# SCH_ESP32-v1_2025-11-18.net
KiCad netlist of a schematic drawn in EasyEDA
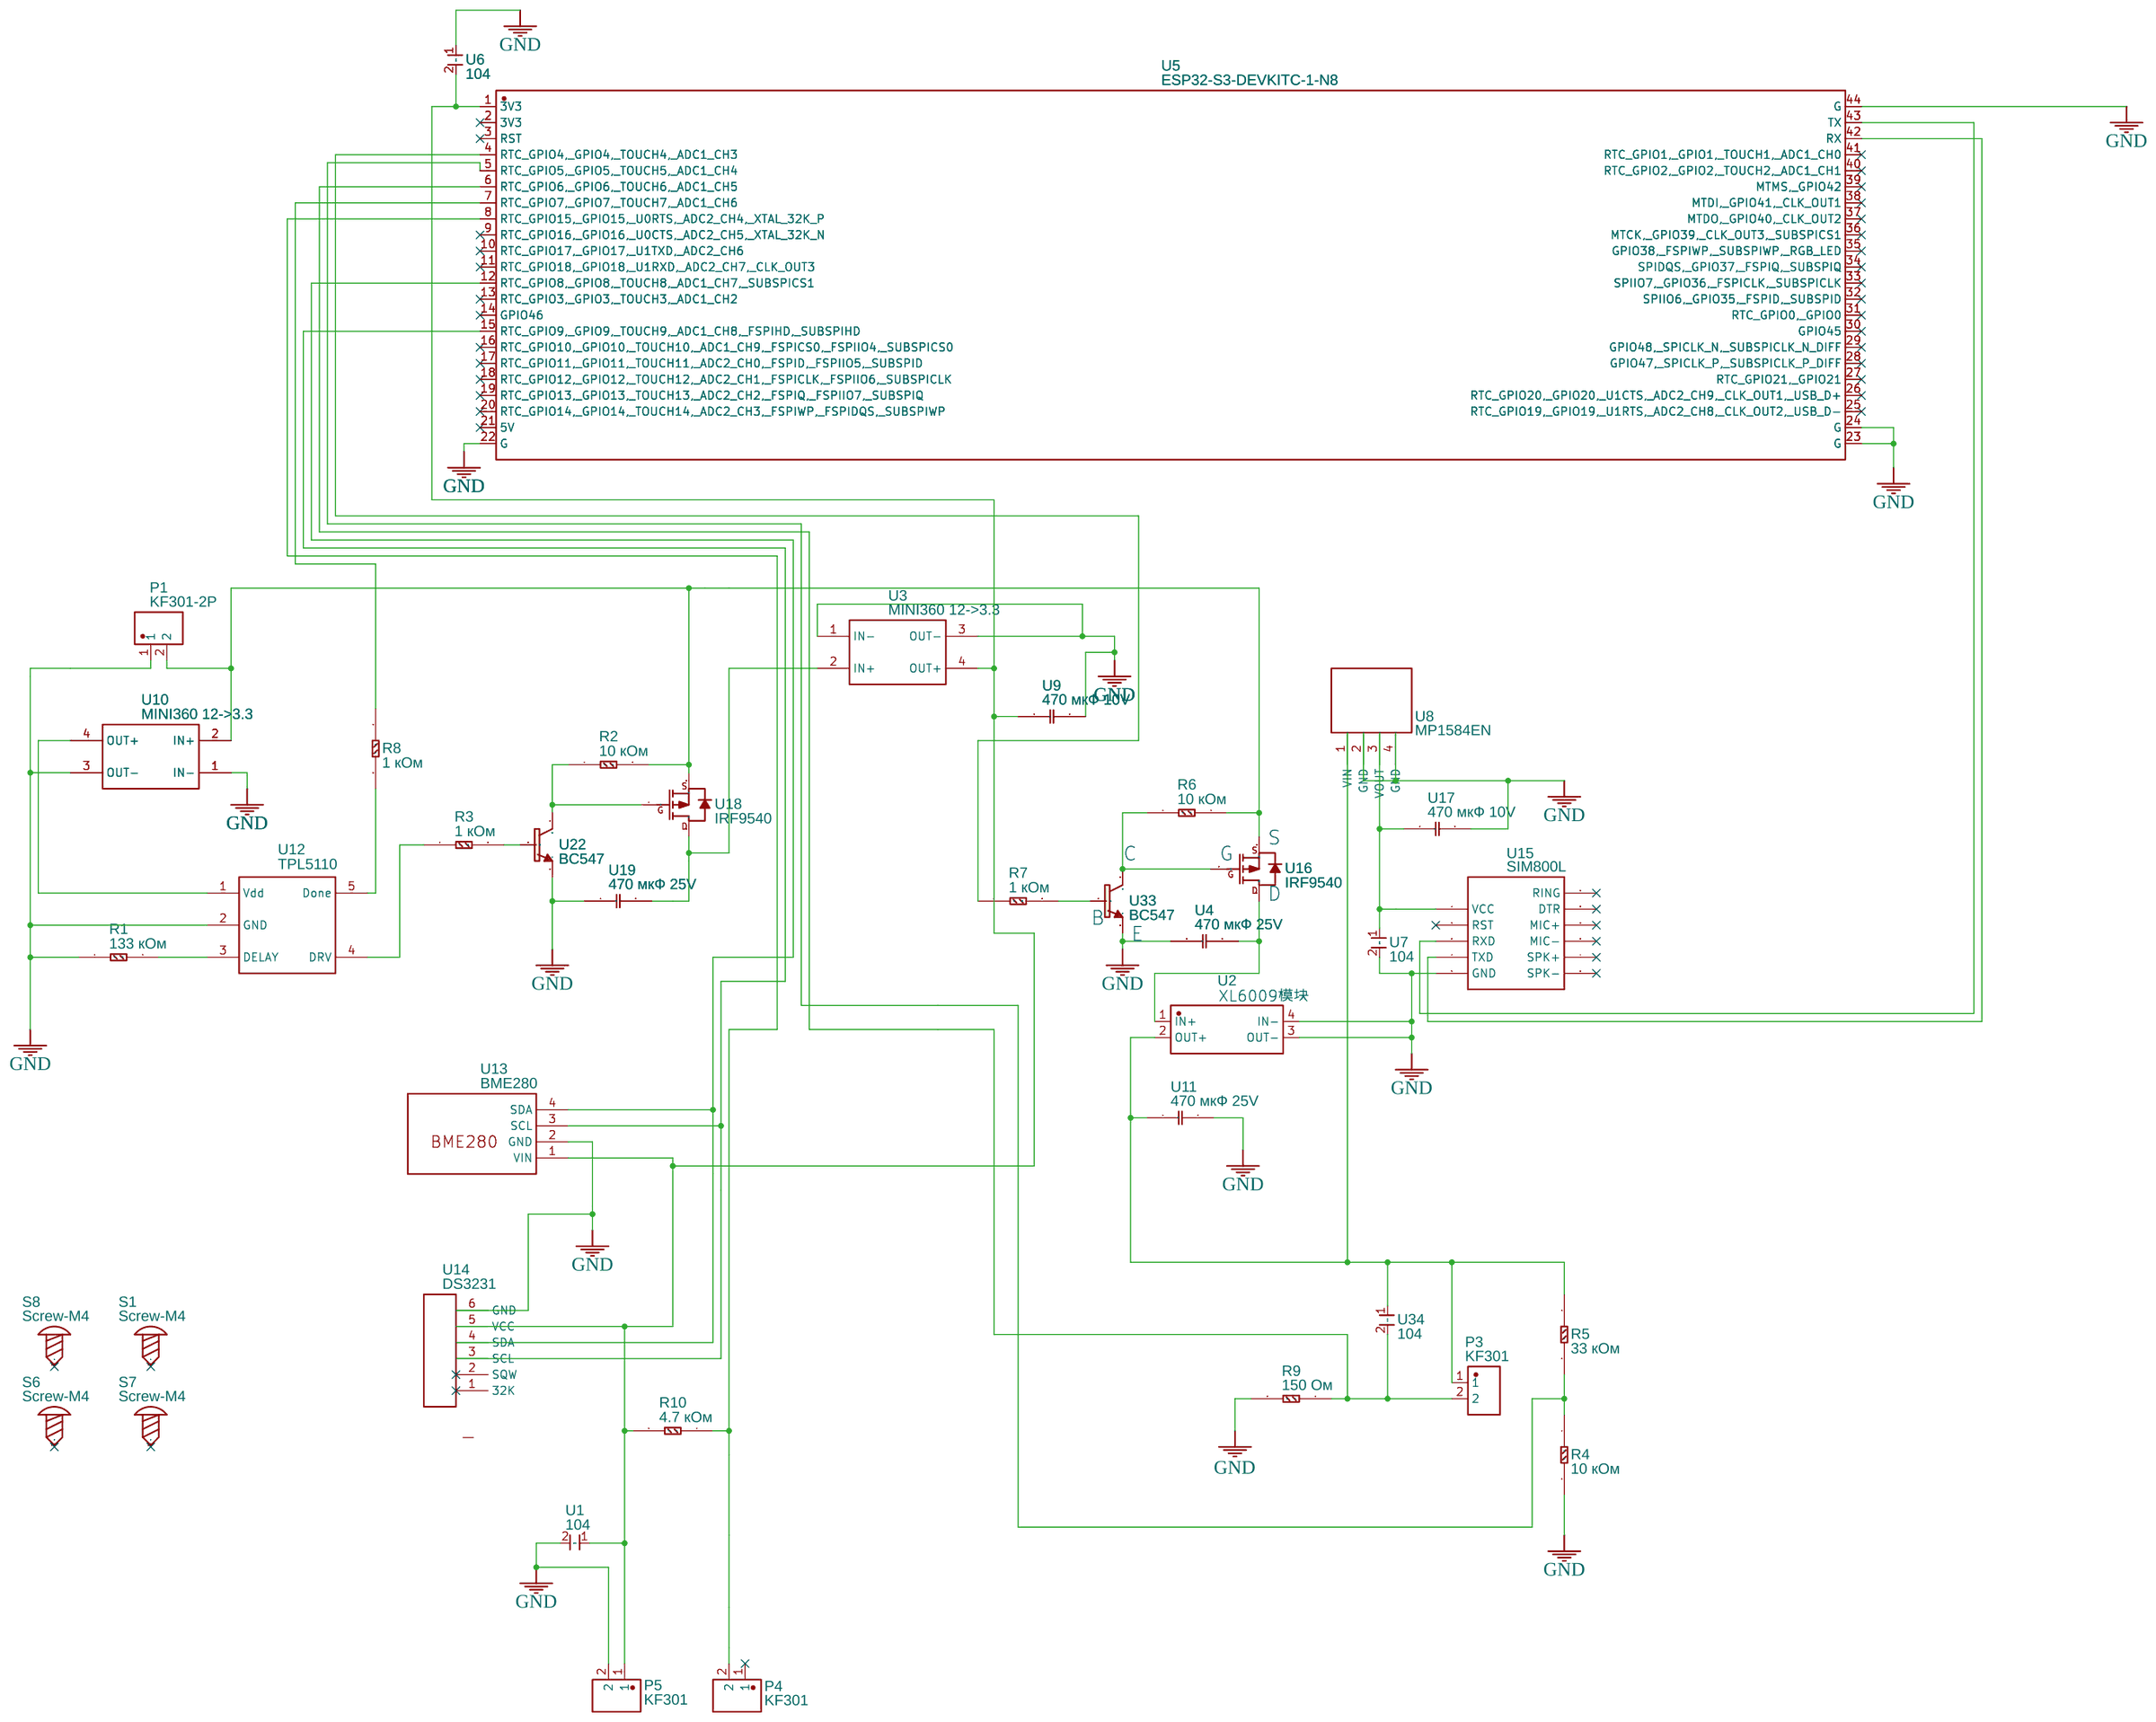
[diagram p0: schematic sheet]

(export (version "E")
  (design (tool "Eeschema 10.0.6"))
  (components
    (comp (ref "P1")
      (value "KF301-2P")
      (fields (field (name "Manufacturer Part") "KF301-2P接线端子"))
      (libsource (lib "") (part "KF301-2P VCC Y GND_2"))
    )
    (comp (ref "P3")
      (value "KF301")
      (fields (field (name "Manufacturer Part") "KF301-2P接线端子"))
      (libsource (lib "") (part "KF301-2P VCC Y GND"))
    )
    (comp (ref "P4")
      (value "KF301")
      (fields (field (name "Manufacturer Part") "KF301-2P接线端子"))
      (libsource (lib "") (part "KF301-2P VCC Y GND_1"))
    )
    (comp (ref "P5")
      (value "KF301")
      (fields (field (name "Manufacturer Part") "KF301-2P接线端子"))
      (libsource (lib "") (part "KF301-2P VCC Y GND_1"))
    )
    (comp (ref "R1") (value "133 кОм") (libsource (lib "") (part "R__1")))
    (comp (ref "R2") (value "10 кОм") (libsource (lib "") (part "R__1")))
    (comp (ref "R3") (value "1 кОм") (libsource (lib "") (part "R__1")))
    (comp (ref "R4") (value "10 кОм") (libsource (lib "") (part "R__2")))
    (comp (ref "R5") (value "33 кОм") (libsource (lib "") (part "R__2")))
    (comp (ref "R6") (value "10 кОм") (libsource (lib "") (part "R__1")))
    (comp (ref "R7") (value "1 кОм") (libsource (lib "") (part "R__1")))
    (comp (ref "R8") (value "1 кОм") (libsource (lib "") (part "R__2")))
    (comp (ref "R9") (value "150 Ом") (libsource (lib "") (part "R_")))
    (comp (ref "R10") (value "4.7 кОм") (libsource (lib "") (part "R_")))
    (comp (ref "S1") (value "Screw-M4") (libsource (lib "") (part "Screw-M4")))
    (comp (ref "S6") (value "Screw-M4") (libsource (lib "") (part "Screw-M4")))
    (comp (ref "S7") (value "Screw-M4") (libsource (lib "") (part "Screw-M4")))
    (comp (ref "S8") (value "Screw-M4") (libsource (lib "") (part "Screw-M4")))
    (comp (ref "U1")
      (value "104")
      (fields (field (name "Manufacturer") "Fe"))
      (libsource (lib "") (part "104_1"))
    )
    (comp (ref "U2")
      (value "XL6009模块")
      (fields (field (name "Manufacturer Part") "xl6009模块"))
      (libsource (lib "") (part "XL6009模块"))
    )
    (comp (ref "U3")
      (value "MINI360 12->3.3")
      (fields (field (name "Manufacturer Part") "Mini360"))
      (libsource (lib "") (part "MINI360BUCK_1"))
    )
    (comp (ref "U4") (value "470 мкФ 25V") (libsource (lib "") (part "C_")))
    (comp (ref "U5")
      (value "ESP32-S3-DEVKITC-1-N8")
      (fields (field (name "Manufacturer") "ESPRESSIF(乐鑫)"))
      (libsource (lib "") (part "ESP32-S3-DEVKITC-1-N8"))
    )
    (comp (ref "U6")
      (value "104")
      (fields (field (name "Manufacturer") "Fe"))
      (libsource (lib "") (part "104"))
    )
    (comp (ref "U7")
      (value "104")
      (fields (field (name "Manufacturer") "Fe"))
      (libsource (lib "") (part "104"))
    )
    (comp (ref "U8") (value "MP1584EN") (libsource (lib "") (part "MP1584EN")))
    (comp (ref "U9") (value "470 мкФ 10V") (libsource (lib "") (part "C_")))
    (comp (ref "U10")
      (value "MINI360 12->3.3")
      (fields (field (name "Manufacturer Part") "Mini360"))
      (libsource (lib "") (part "MINI360BUCK"))
    )
    (comp (ref "U11") (value "470 мкФ 25V") (libsource (lib "") (part "C_")))
    (comp (ref "U12")
      (value "TPL5110")
      (fields (field (name "Manufacturer Part") "3435"))
      (libsource (lib "") (part "ADAFRUIT TPL5110 BREAKOUT"))
    )
    (comp (ref "U13") (value "BME280") (libsource (lib "") (part "BME280")))
    (comp (ref "U14") (value "DS3231") (libsource (lib "") (part "DS3231 upright")))
    (comp (ref "U15") (value "SIM800L") (libsource (lib "") (part "SIM800L")))
    (comp (ref "U16") (value "IRF9540") (libsource (lib "") (part "IRF9540")))
    (comp (ref "U17") (value "470 мкФ 10V") (libsource (lib "") (part "C_")))
    (comp (ref "U18") (value "IRF9540") (libsource (lib "") (part "IRF9540")))
    (comp (ref "U19") (value "470 мкФ 25V") (libsource (lib "") (part "C_")))
    (comp (ref "U22") (value "BC547") (libsource (lib "") (part "BC547")))
    (comp (ref "U33") (value "BC547") (libsource (lib "") (part "BC547")))
    (comp (ref "U34")
      (value "104")
      (fields (field (name "Manufacturer") "Fe"))
      (libsource (lib "") (part "104"))
    )
  )
  (nets
    (net (code "1") (name "GND") (class "Default")
      (node (ref "P1") (pin "1") (pinfunction "1_1") (pintype "unspecified"))
      (node (ref "P5") (pin "2") (pinfunction "2_2") (pintype "unspecified"))
      (node (ref "R1") (pin "1") (pinfunction "1_1") (pintype "unspecified"))
      (node (ref "R4") (pin "2") (pinfunction "2_2") (pintype "unspecified"))
      (node (ref "R9") (pin "2") (pinfunction "2_2") (pintype "unspecified"))
      (node (ref "U1") (pin "2") (pinfunction "2_2") (pintype "unspecified"))
      (node (ref "U10") (pin "1") (pinfunction "IN-_1") (pintype "unspecified"))
      (node (ref "U10") (pin "3") (pinfunction "OUT-_3") (pintype "unspecified"))
      (node (ref "U11") (pin "2") (pinfunction "2_2") (pintype "unspecified"))
      (node (ref "U12") (pin "2") (pinfunction "GND_2") (pintype "unspecified"))
      (node (ref "U13") (pin "2") (pinfunction "GND_2") (pintype "unspecified"))
      (node (ref "U14") (pin "6") (pinfunction "GND_6") (pintype "unspecified"))
      (node (ref "U15") (pin "5") (pinfunction "GND_5") (pintype "unspecified"))
      (node (ref "U17") (pin "2") (pinfunction "2_2") (pintype "unspecified"))
      (node (ref "U19") (pin "1") (pinfunction "1_1") (pintype "unspecified"))
      (node (ref "U2") (pin "3") (pinfunction "OUT-_3") (pintype "unspecified"))
      (node (ref "U2") (pin "4") (pinfunction "IN-_4") (pintype "unspecified"))
      (node (ref "U22") (pin "3") (pinfunction "E_3") (pintype "unspecified"))
      (node (ref "U3") (pin "1") (pinfunction "IN-_1") (pintype "unspecified"))
      (node (ref "U3") (pin "3") (pinfunction "OUT-_3") (pintype "unspecified"))
      (node (ref "U33") (pin "3") (pinfunction "E_3") (pintype "unspecified"))
      (node (ref "U4") (pin "1") (pinfunction "1_1") (pintype "unspecified"))
      (node (ref "U5") (pin "22") (pinfunction "G_22") (pintype "unspecified"))
      (node (ref "U5") (pin "23") (pinfunction "G_23") (pintype "unspecified"))
      (node (ref "U5") (pin "24") (pinfunction "G_24") (pintype "unspecified"))
      (node (ref "U5") (pin "44") (pinfunction "G_44") (pintype "unspecified"))
      (node (ref "U6") (pin "1") (pinfunction "1_1") (pintype "unspecified"))
      (node (ref "U7") (pin "2") (pinfunction "2_2") (pintype "unspecified"))
      (node (ref "U8") (pin "2") (pinfunction "GND_2") (pintype "unspecified"))
      (node (ref "U8") (pin "4") (pinfunction "GND_4") (pintype "unspecified"))
      (node (ref "U9") (pin "2") (pinfunction "2_2") (pintype "unspecified"))
    )
    (net (code "2") (name "Net-(U2-OUT+)") (class "Default")
      (node (ref "P3") (pin "1") (pinfunction "1_1") (pintype "unspecified"))
      (node (ref "R5") (pin "1") (pinfunction "1_1") (pintype "unspecified"))
      (node (ref "U11") (pin "1") (pinfunction "1_1") (pintype "unspecified"))
      (node (ref "U2") (pin "2") (pinfunction "OUT+_2") (pintype "unspecified"))
      (node (ref "U34") (pin "1") (pinfunction "1_1") (pintype "unspecified"))
      (node (ref "U8") (pin "1") (pinfunction "VIN_1") (pintype "unspecified"))
    )
    (net (code "3") (name "Net-(U5-RTC_GPIO4,_GPIO4,_TOUCH4,_ADC1_CH3)") (class "Default")
      (node (ref "R7") (pin "1") (pinfunction "1_1") (pintype "unspecified"))
      (node (ref "U5") (pin "4") (pinfunction "RTC_GPIO4,_GPIO4,_TOUCH4,_ADC1_CH3_4") (pintype "unspecified"))
    )
    (net (code "4") (name "Net-(U5-RTC_GPIO5,_GPIO5,_TOUCH5,_ADC1_CH4)") (class "Default")
      (node (ref "R4") (pin "1") (pinfunction "1_1") (pintype "unspecified"))
      (node (ref "R5") (pin "2") (pinfunction "2_2") (pintype "unspecified"))
      (node (ref "U5") (pin "5") (pinfunction "RTC_GPIO5,_GPIO5,_TOUCH5,_ADC1_CH4_5") (pintype "unspecified"))
    )
    (net (code "5") (name "Net-(U5-RTC_GPIO6,_GPIO6,_TOUCH6,_ADC1_CH5)") (class "Default")
      (node (ref "P3") (pin "2") (pinfunction "2_2") (pintype "unspecified"))
      (node (ref "R9") (pin "1") (pinfunction "1_1") (pintype "unspecified"))
      (node (ref "U34") (pin "2") (pinfunction "2_2") (pintype "unspecified"))
      (node (ref "U5") (pin "6") (pinfunction "RTC_GPIO6,_GPIO6,_TOUCH6,_ADC1_CH5_6") (pintype "unspecified"))
    )
    (net (code "6") (name "Net-(U5-RTC_GPIO7,_GPIO7,_TOUCH7,_ADC1_CH6)") (class "Default")
      (node (ref "R8") (pin "1") (pinfunction "1_1") (pintype "unspecified"))
      (node (ref "U5") (pin "7") (pinfunction "RTC_GPIO7,_GPIO7,_TOUCH7,_ADC1_CH6_7") (pintype "unspecified"))
    )
    (net (code "7") (name "Net-(U5-RTC_GPIO15,_GPIO15,_U0RTS,_ADC2_CH4,_XTAL_32K_P)") (class "Default")
      (node (ref "P4") (pin "2") (pinfunction "2_2") (pintype "unspecified"))
      (node (ref "R10") (pin "1") (pinfunction "1_1") (pintype "unspecified"))
      (node (ref "U5") (pin "8") (pinfunction "RTC_GPIO15,_GPIO15,_U0RTS,_ADC2_CH4,_XTAL_32K_P_8") (pintype "unspecified"))
    )
    (net (code "8") (name "Net-(U10-IN+)") (class "Default")
      (node (ref "P1") (pin "2") (pinfunction "2_2") (pintype "unspecified"))
      (node (ref "R2") (pin "2") (pinfunction "2_2") (pintype "unspecified"))
      (node (ref "R6") (pin "2") (pinfunction "2_2") (pintype "unspecified"))
      (node (ref "U10") (pin "2") (pinfunction "IN+_2") (pintype "unspecified"))
      (node (ref "U16") (pin "3") (pinfunction "S_3") (pintype "unspecified"))
      (node (ref "U18") (pin "3") (pinfunction "S_3") (pintype "unspecified"))
    )
    (net (code "9") (name "Net-(U10-OUT+)") (class "Default")
      (node (ref "U10") (pin "4") (pinfunction "OUT+_4") (pintype "unspecified"))
      (node (ref "U12") (pin "1") (pinfunction "Vdd_1") (pintype "unspecified"))
    )
    (net (code "10") (name "Net-(U12-DELAY)") (class "Default")
      (node (ref "R1") (pin "2") (pinfunction "2_2") (pintype "unspecified"))
      (node (ref "U12") (pin "3") (pinfunction "DELAY_3") (pintype "unspecified"))
    )
    (net (code "11") (name "Net-(U12-DRV)") (class "Default")
      (node (ref "R3") (pin "1") (pinfunction "1_1") (pintype "unspecified"))
      (node (ref "U12") (pin "4") (pinfunction "DRV_4") (pintype "unspecified"))
    )
    (net (code "12") (name "Net-(U12-Done)") (class "Default")
      (node (ref "R8") (pin "2") (pinfunction "2_2") (pintype "unspecified"))
      (node (ref "U12") (pin "5") (pinfunction "Done_5") (pintype "unspecified"))
    )
    (net (code "13") (name "Net-(U13-SCL)") (class "Default")
      (node (ref "U13") (pin "3") (pinfunction "SCL_3") (pintype "unspecified"))
      (node (ref "U14") (pin "3") (pinfunction "SCL_3") (pintype "unspecified"))
      (node (ref "U5") (pin "15") (pinfunction "RTC_GPIO9,_GPIO9,_TOUCH9,_ADC1_CH8,_FSPIHD,_SUBSPIHD_15") (pintype "unspecified"))
    )
    (net (code "14") (name "Net-(U13-SDA)") (class "Default")
      (node (ref "U13") (pin "4") (pinfunction "SDA_4") (pintype "unspecified"))
      (node (ref "U14") (pin "4") (pinfunction "SDA_4") (pintype "unspecified"))
      (node (ref "U5") (pin "12") (pinfunction "RTC_GPIO8,_GPIO8,_TOUCH8,_ADC1_CH7,_SUBSPICS1_12") (pintype "unspecified"))
    )
    (net (code "15") (name "Net-(U13-VIN)") (class "Default")
      (node (ref "P5") (pin "1") (pinfunction "1_1") (pintype "unspecified"))
      (node (ref "R10") (pin "2") (pinfunction "2_2") (pintype "unspecified"))
      (node (ref "U1") (pin "1") (pinfunction "1_1") (pintype "unspecified"))
      (node (ref "U13") (pin "1") (pinfunction "VIN_1") (pintype "unspecified"))
      (node (ref "U14") (pin "5") (pinfunction "VCC_5") (pintype "unspecified"))
      (node (ref "U3") (pin "4") (pinfunction "OUT+_4") (pintype "unspecified"))
      (node (ref "U5") (pin "1") (pinfunction "3V3_1") (pintype "unspecified"))
      (node (ref "U6") (pin "2") (pinfunction "2_2") (pintype "unspecified"))
      (node (ref "U9") (pin "1") (pinfunction "1_1") (pintype "unspecified"))
    )
    (net (code "16") (name "Net-(U15-RXD)") (class "Default")
      (node (ref "U15") (pin "3") (pinfunction "RXD_3") (pintype "unspecified"))
      (node (ref "U5") (pin "43") (pinfunction "TX_43") (pintype "unspecified"))
    )
    (net (code "17") (name "Net-(U15-TXD)") (class "Default")
      (node (ref "U15") (pin "4") (pinfunction "TXD_4") (pintype "unspecified"))
      (node (ref "U5") (pin "42") (pinfunction "RX_42") (pintype "unspecified"))
    )
    (net (code "18") (name "Net-(U15-VCC)") (class "Default")
      (node (ref "U15") (pin "1") (pinfunction "VCC_1") (pintype "unspecified"))
      (node (ref "U17") (pin "1") (pinfunction "1_1") (pintype "unspecified"))
      (node (ref "U7") (pin "1") (pinfunction "1_1") (pintype "unspecified"))
      (node (ref "U8") (pin "3") (pinfunction "VOUT_3") (pintype "unspecified"))
    )
    (net (code "19") (name "Net-(U16-D)") (class "Default")
      (node (ref "U16") (pin "2") (pinfunction "D_2") (pintype "unspecified"))
      (node (ref "U2") (pin "1") (pinfunction "IN+_1") (pintype "unspecified"))
      (node (ref "U4") (pin "2") (pinfunction "2_2") (pintype "unspecified"))
    )
    (net (code "20") (name "Net-(U16-G)") (class "Default")
      (node (ref "R6") (pin "1") (pinfunction "1_1") (pintype "unspecified"))
      (node (ref "U16") (pin "1") (pinfunction "G_1") (pintype "unspecified"))
      (node (ref "U33") (pin "1") (pinfunction "C_1") (pintype "unspecified"))
    )
    (net (code "21") (name "Net-(U18-D)") (class "Default")
      (node (ref "U18") (pin "2") (pinfunction "D_2") (pintype "unspecified"))
      (node (ref "U19") (pin "2") (pinfunction "2_2") (pintype "unspecified"))
      (node (ref "U3") (pin "2") (pinfunction "IN+_2") (pintype "unspecified"))
    )
    (net (code "22") (name "Net-(U18-G)") (class "Default")
      (node (ref "R2") (pin "1") (pinfunction "1_1") (pintype "unspecified"))
      (node (ref "U18") (pin "1") (pinfunction "G_1") (pintype "unspecified"))
      (node (ref "U22") (pin "1") (pinfunction "C_1") (pintype "unspecified"))
    )
    (net (code "23") (name "Net-(U22-B)") (class "Default")
      (node (ref "R3") (pin "2") (pinfunction "2_2") (pintype "unspecified"))
      (node (ref "U22") (pin "2") (pinfunction "B_2") (pintype "unspecified"))
    )
    (net (code "24") (name "Net-(U33-B)") (class "Default")
      (node (ref "R7") (pin "2") (pinfunction "2_2") (pintype "unspecified"))
      (node (ref "U33") (pin "2") (pinfunction "B_2") (pintype "unspecified"))
    )
    (net (code "25") (name "unconnected-(P4-Pad1)") (class "Default")
      (node (ref "P4") (pin "1") (pinfunction "1_1") (pintype "unspecified+no_connect"))
    )
    (net (code "26") (name "unconnected-(S1-Pad1)") (class "Default")
      (node (ref "S1") (pin "1") (pinfunction "1_1") (pintype "unspecified+no_connect"))
    )
    (net (code "27") (name "unconnected-(S6-Pad1)") (class "Default")
      (node (ref "S6") (pin "1") (pinfunction "1_1") (pintype "unspecified+no_connect"))
    )
    (net (code "28") (name "unconnected-(S7-Pad1)") (class "Default")
      (node (ref "S7") (pin "1") (pinfunction "1_1") (pintype "unspecified+no_connect"))
    )
    (net (code "29") (name "unconnected-(S8-Pad1)") (class "Default")
      (node (ref "S8") (pin "1") (pinfunction "1_1") (pintype "unspecified+no_connect"))
    )
    (net (code "30") (name "unconnected-(U5-3V3-Pad2)") (class "Default")
      (node (ref "U5") (pin "2") (pinfunction "3V3_2") (pintype "unspecified+no_connect"))
    )
    (net (code "31") (name "unconnected-(U5-5V-Pad21)") (class "Default")
      (node (ref "U5") (pin "21") (pinfunction "5V_21") (pintype "unspecified+no_connect"))
    )
    (net (code "32") (name "unconnected-(U5-GPIO38,_FSPIWP,_SUBSPIWP,_RGB_LED-Pad35)") (class "Default")
      (node (ref "U5") (pin "35") (pinfunction "GPIO38,_FSPIWP,_SUBSPIWP,_RGB_LED_35") (pintype "unspecified+no_connect"))
    )
    (net (code "33") (name "unconnected-(U5-GPIO45-Pad30)") (class "Default")
      (node (ref "U5") (pin "30") (pinfunction "GPIO45_30") (pintype "unspecified+no_connect"))
    )
    (net (code "34") (name "unconnected-(U5-GPIO46-Pad14)") (class "Default")
      (node (ref "U5") (pin "14") (pinfunction "GPIO46_14") (pintype "unspecified+no_connect"))
    )
    (net (code "35") (name "unconnected-(U5-GPIO47,_SPICLK_P,_SUBSPICLK_P_DIFF-Pad28)") (class "Default")
      (node (ref "U5") (pin "28") (pinfunction "GPIO47,_SPICLK_P,_SUBSPICLK_P_DIFF_28") (pintype "unspecified+no_connect"))
    )
    (net (code "36") (name "unconnected-(U5-GPIO48,_SPICLK_N,_SUBSPICLK_N_DIFF-Pad29)") (class "Default")
      (node (ref "U5") (pin "29") (pinfunction "GPIO48,_SPICLK_N,_SUBSPICLK_N_DIFF_29") (pintype "unspecified+no_connect"))
    )
    (net (code "37") (name "unconnected-(U5-MTCK,_GPIO39,_CLK_OUT3,_SUBSPICS1-Pad36)") (class "Default")
      (node (ref "U5") (pin "36") (pinfunction "MTCK,_GPIO39,_CLK_OUT3,_SUBSPICS1_36") (pintype "unspecified+no_connect"))
    )
    (net (code "38") (name "unconnected-(U5-MTDI,_GPIO41,_CLK_OUT1-Pad38)") (class "Default")
      (node (ref "U5") (pin "38") (pinfunction "MTDI,_GPIO41,_CLK_OUT1_38") (pintype "unspecified+no_connect"))
    )
    (net (code "39") (name "unconnected-(U5-MTDO,_GPIO40,_CLK_OUT2-Pad37)") (class "Default")
      (node (ref "U5") (pin "37") (pinfunction "MTDO,_GPIO40,_CLK_OUT2_37") (pintype "unspecified+no_connect"))
    )
    (net (code "40") (name "unconnected-(U5-MTMS,_GPIO42-Pad39)") (class "Default")
      (node (ref "U5") (pin "39") (pinfunction "MTMS,_GPIO42_39") (pintype "unspecified+no_connect"))
    )
    (net (code "41") (name "unconnected-(U5-RST-Pad3)") (class "Default")
      (node (ref "U5") (pin "3") (pinfunction "RST_3") (pintype "unspecified+no_connect"))
    )
    (net (code "42") (name "unconnected-(U5-RTC_GPIO0,_GPIO0-Pad31)") (class "Default")
      (node (ref "U5") (pin "31") (pinfunction "RTC_GPIO0,_GPIO0_31") (pintype "unspecified+no_connect"))
    )
    (net (code "43") (name "unconnected-(U5-RTC_GPIO1,_GPIO1,_TOUCH1,_ADC1_CH0-Pad41)") (class "Default")
      (node (ref "U5") (pin "41") (pinfunction "RTC_GPIO1,_GPIO1,_TOUCH1,_ADC1_CH0_41") (pintype "unspecified+no_connect"))
    )
    (net (code "44") (name "unconnected-(U5-RTC_GPIO2,_GPIO2,_TOUCH2,_ADC1_CH1-Pad40)") (class "Default")
      (node (ref "U5") (pin "40") (pinfunction "RTC_GPIO2,_GPIO2,_TOUCH2,_ADC1_CH1_40") (pintype "unspecified+no_connect"))
    )
    (net (code "45") (name "unconnected-(U5-RTC_GPIO3,_GPIO3,_TOUCH3,_ADC1_CH2-Pad13)") (class "Default")
      (node (ref "U5") (pin "13") (pinfunction "RTC_GPIO3,_GPIO3,_TOUCH3,_ADC1_CH2_13") (pintype "unspecified+no_connect"))
    )
    (net (code "46") (name "unconnected-(U5-RTC_GPIO10,_GPIO10,_TOUCH10,_ADC1_CH9,_FSPICS0,_FSPIIO4,_SUBSPICS0-Pad16)") (class "Default")
      (node (ref "U5") (pin "16") (pinfunction "RTC_GPIO10,_GPIO10,_TOUCH10,_ADC1_CH9,_FSPICS0,_FSPIIO4,_SUBSPICS0_16") (pintype "unspecified+no_connect"))
    )
    (net (code "47") (name "unconnected-(U5-RTC_GPIO11,_GPIO11,_TOUCH11,_ADC2_CH0,_FSPID,_FSPIIO5,_SUBSPID-Pad17)") (class "Default")
      (node (ref "U5") (pin "17") (pinfunction "RTC_GPIO11,_GPIO11,_TOUCH11,_ADC2_CH0,_FSPID,_FSPIIO5,_SUBSPID_17") (pintype "unspecified+no_connect"))
    )
    (net (code "48") (name "unconnected-(U5-RTC_GPIO12,_GPIO12,_TOUCH12,_ADC2_CH1,_FSPICLK,_FSPIIO6,_SUBSPICLK-Pad18)") (class "Default")
      (node (ref "U5") (pin "18") (pinfunction "RTC_GPIO12,_GPIO12,_TOUCH12,_ADC2_CH1,_FSPICLK,_FSPIIO6,_SUBSPICLK_18") (pintype "unspecified+no_connect"))
    )
    (net (code "49") (name "unconnected-(U5-RTC_GPIO13,_GPIO13,_TOUCH13,_ADC2_CH2,_FSPIQ,_FSPIIO7,_SUBSPIQ-Pad19)") (class "Default")
      (node (ref "U5") (pin "19") (pinfunction "RTC_GPIO13,_GPIO13,_TOUCH13,_ADC2_CH2,_FSPIQ,_FSPIIO7,_SUBSPIQ_19") (pintype "unspecified+no_connect"))
    )
    (net (code "50") (name "unconnected-(U5-RTC_GPIO14,_GPIO14,_TOUCH14,_ADC2_CH3,_FSPIWP,_FSPIDQS,_SUBSPIWP-Pad20)") (class "Default")
      (node (ref "U5") (pin "20") (pinfunction "RTC_GPIO14,_GPIO14,_TOUCH14,_ADC2_CH3,_FSPIWP,_FSPIDQS,_SUBSPIWP_20") (pintype "unspecified+no_connect"))
    )
    (net (code "51") (name "unconnected-(U5-RTC_GPIO16,_GPIO16,_U0CTS,_ADC2_CH5,_XTAL_32K_N-Pad9)") (class "Default")
      (node (ref "U5") (pin "9") (pinfunction "RTC_GPIO16,_GPIO16,_U0CTS,_ADC2_CH5,_XTAL_32K_N_9") (pintype "unspecified+no_connect"))
    )
    (net (code "52") (name "unconnected-(U5-RTC_GPIO17,_GPIO17,_U1TXD,_ADC2_CH6-Pad10)") (class "Default")
      (node (ref "U5") (pin "10") (pinfunction "RTC_GPIO17,_GPIO17,_U1TXD,_ADC2_CH6_10") (pintype "unspecified+no_connect"))
    )
    (net (code "53") (name "unconnected-(U5-RTC_GPIO18,_GPIO18,_U1RXD,_ADC2_CH7,_CLK_OUT3-Pad11)") (class "Default")
      (node (ref "U5") (pin "11") (pinfunction "RTC_GPIO18,_GPIO18,_U1RXD,_ADC2_CH7,_CLK_OUT3_11") (pintype "unspecified+no_connect"))
    )
    (net (code "54") (name "unconnected-(U5-RTC_GPIO19,_GPIO19,_U1RTS,_ADC2_CH8,_CLK_OUT2,_USB_D--Pad25)") (class "Default")
      (node (ref "U5") (pin "25") (pinfunction "RTC_GPIO19,_GPIO19,_U1RTS,_ADC2_CH8,_CLK_OUT2,_USB_D-_25") (pintype "unspecified+no_connect"))
    )
    (net (code "55") (name "unconnected-(U5-RTC_GPIO20,_GPIO20,_U1CTS,_ADC2_CH9,_CLK_OUT1,_USB_D+-Pad26)") (class "Default")
      (node (ref "U5") (pin "26") (pinfunction "RTC_GPIO20,_GPIO20,_U1CTS,_ADC2_CH9,_CLK_OUT1,_USB_D+_26") (pintype "unspecified+no_connect"))
    )
    (net (code "56") (name "unconnected-(U5-RTC_GPIO21,_GPIO21-Pad27)") (class "Default")
      (node (ref "U5") (pin "27") (pinfunction "RTC_GPIO21,_GPIO21_27") (pintype "unspecified+no_connect"))
    )
    (net (code "57") (name "unconnected-(U5-SPIDQS,_GPIO37,_FSPIQ,_SUBSPIQ-Pad34)") (class "Default")
      (node (ref "U5") (pin "34") (pinfunction "SPIDQS,_GPIO37,_FSPIQ,_SUBSPIQ_34") (pintype "unspecified+no_connect"))
    )
    (net (code "58") (name "unconnected-(U5-SPIIO6,_GPIO35,_FSPID,_SUBSPID-Pad32)") (class "Default")
      (node (ref "U5") (pin "32") (pinfunction "SPIIO6,_GPIO35,_FSPID,_SUBSPID_32") (pintype "unspecified+no_connect"))
    )
    (net (code "59") (name "unconnected-(U5-SPIIO7,_GPIO36,_FSPICLK,_SUBSPICLK-Pad33)") (class "Default")
      (node (ref "U5") (pin "33") (pinfunction "SPIIO7,_GPIO36,_FSPICLK,_SUBSPICLK_33") (pintype "unspecified+no_connect"))
    )
    (net (code "60") (name "unconnected-(U14-32K-Pad1)") (class "Default")
      (node (ref "U14") (pin "1") (pinfunction "32K_1") (pintype "unspecified+no_connect"))
    )
    (net (code "61") (name "unconnected-(U14-SQW-Pad2)") (class "Default")
      (node (ref "U14") (pin "2") (pinfunction "SQW_2") (pintype "unspecified+no_connect"))
    )
    (net (code "62") (name "unconnected-(U15-DTR-Pad10)") (class "Default")
      (node (ref "U15") (pin "10") (pinfunction "DTR_10") (pintype "unspecified+no_connect"))
    )
    (net (code "63") (name "unconnected-(U15-MIC+-Pad9)") (class "Default")
      (node (ref "U15") (pin "9") (pinfunction "MIC+_9") (pintype "unspecified+no_connect"))
    )
    (net (code "64") (name "unconnected-(U15-MIC--Pad8)") (class "Default")
      (node (ref "U15") (pin "8") (pinfunction "MIC-_8") (pintype "unspecified+no_connect"))
    )
    (net (code "65") (name "unconnected-(U15-RING-Pad11)") (class "Default")
      (node (ref "U15") (pin "11") (pinfunction "RING_11") (pintype "unspecified+no_connect"))
    )
    (net (code "66") (name "unconnected-(U15-RST-Pad2)") (class "Default")
      (node (ref "U15") (pin "2") (pinfunction "RST_2") (pintype "unspecified+no_connect"))
    )
    (net (code "67") (name "unconnected-(U15-SPK+-Pad7)") (class "Default")
      (node (ref "U15") (pin "7") (pinfunction "SPK+_7") (pintype "unspecified+no_connect"))
    )
    (net (code "68") (name "unconnected-(U15-SPK--Pad6)") (class "Default")
      (node (ref "U15") (pin "6") (pinfunction "SPK-_6") (pintype "unspecified+no_connect"))
    )
  )
)
